# LED_Chaser.net
KiCad netlist of a schematic drawn in Altium Designer
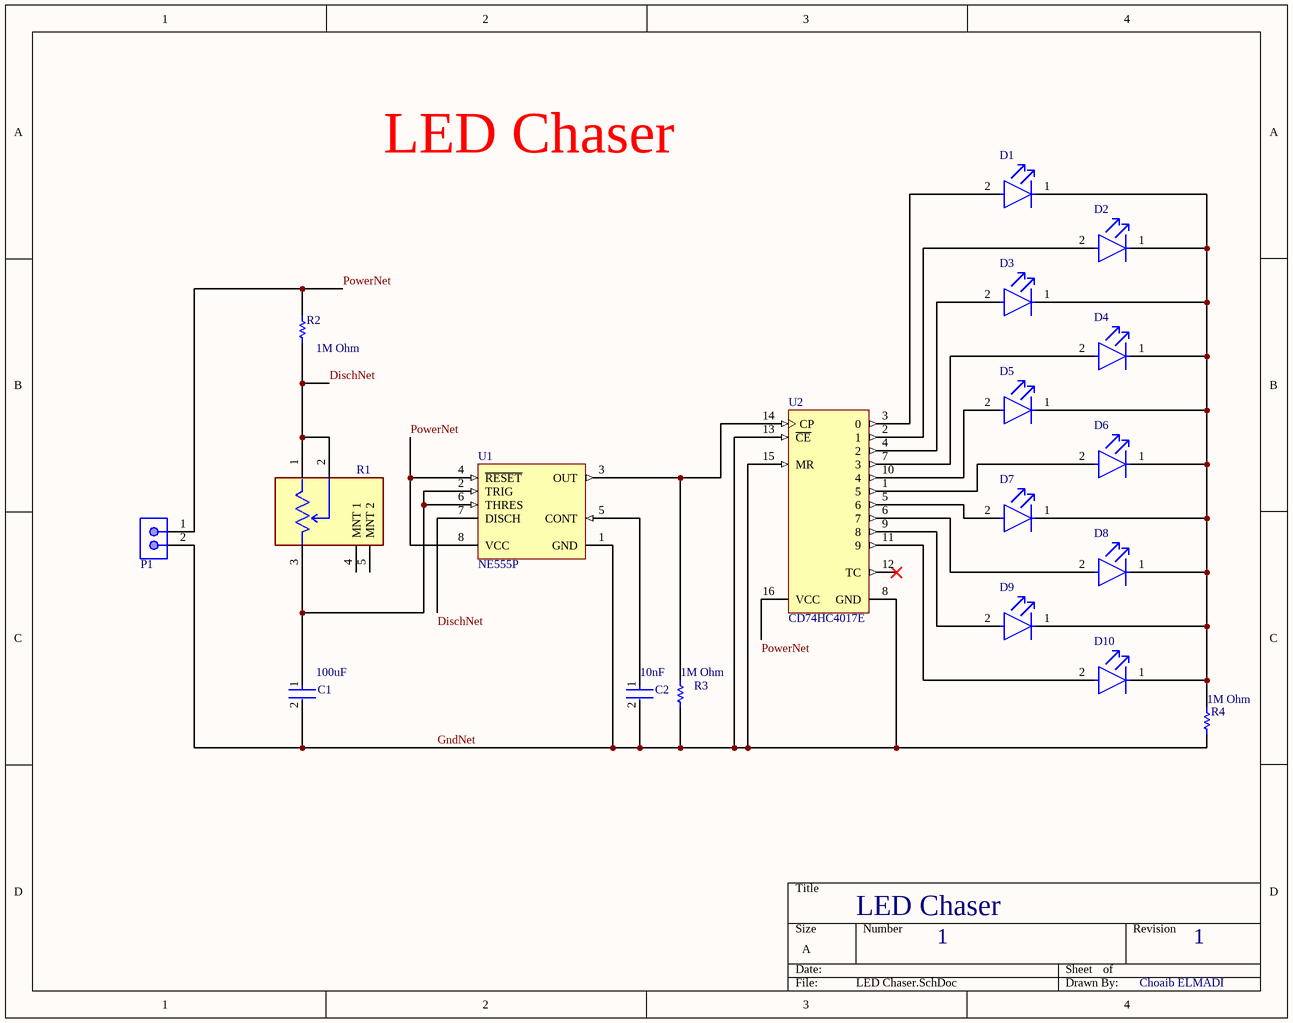
[diagram p0: LED Chaser.SchDoc]

(export (version "E")
  (design (tool "Eeschema 10.0.6"))
  (components
    (comp (ref "C1")
      (value "GRM32ER60J107ME20L")
      (footprint "FP-GRM32-0_3-MFG")
      (description "CAP CER 100UF 6.3V X5R 1210")
      (fields
        (field (name "OCTOPART") "https://octopart.com/grm32er60j107me20l-murata-197007")
        (field (name "3DS PART NUMBER") "220-00002")
        (field (name "CAPACITANCE") "100uF")
      )
      (libsource (lib "Altium Content Vault") (part "11868f565c42a9108669ba33697ecf6"))
    )
    (comp (ref "C2")
      (value "GRM32ER60J107ME20L")
      (footprint "FP-GRM32-0_3-MFG")
      (description "CAP CER 100UF 6.3V X5R 1210")
      (fields
        (field (name "OCTOPART") "https://octopart.com/grm32er60j107me20l-murata-197007")
        (field (name "3DS PART NUMBER") "220-00002")
        (field (name "CAPACITANCE") "10nF")
      )
      (libsource (lib "Altium Content Vault") (part "11868f565c42a9108669ba33697ecf6"))
    )
    (comp (ref "D1")
      (value "TLHR4400")
      (footprint "FP-6_544-5255_01-4-MFG")
      (description "TLHR4400 LED; Red; 3mcd; 3mmDia.; T-1; 30mA; 2V; 635nm; +/-30deg; GaAsP on GaP; 15V; 100mW")
      (libsource (lib "Altium Content Vault") (part "8706943c75ba83719d021d2fdc84c58"))
    )
    (comp (ref "D2")
      (value "TLHR4400")
      (footprint "FP-6_544-5255_01-4-MFG")
      (description "TLHR4400 LED; Red; 3mcd; 3mmDia.; T-1; 30mA; 2V; 635nm; +/-30deg; GaAsP on GaP; 15V; 100mW")
      (libsource (lib "Altium Content Vault") (part "8706943c75ba83719d021d2fdc84c58"))
    )
    (comp (ref "D3")
      (value "TLHR4400")
      (footprint "FP-6_544-5255_01-4-MFG")
      (description "TLHR4400 LED; Red; 3mcd; 3mmDia.; T-1; 30mA; 2V; 635nm; +/-30deg; GaAsP on GaP; 15V; 100mW")
      (libsource (lib "Altium Content Vault") (part "8706943c75ba83719d021d2fdc84c58"))
    )
    (comp (ref "D4")
      (value "TLHR4400")
      (footprint "FP-6_544-5255_01-4-MFG")
      (description "TLHR4400 LED; Red; 3mcd; 3mmDia.; T-1; 30mA; 2V; 635nm; +/-30deg; GaAsP on GaP; 15V; 100mW")
      (libsource (lib "Altium Content Vault") (part "8706943c75ba83719d021d2fdc84c58"))
    )
    (comp (ref "D5")
      (value "TLHR4400")
      (footprint "FP-6_544-5255_01-4-MFG")
      (description "TLHR4400 LED; Red; 3mcd; 3mmDia.; T-1; 30mA; 2V; 635nm; +/-30deg; GaAsP on GaP; 15V; 100mW")
      (libsource (lib "Altium Content Vault") (part "8706943c75ba83719d021d2fdc84c58"))
    )
    (comp (ref "D6")
      (value "TLHR4400")
      (footprint "FP-6_544-5255_01-4-MFG")
      (description "TLHR4400 LED; Red; 3mcd; 3mmDia.; T-1; 30mA; 2V; 635nm; +/-30deg; GaAsP on GaP; 15V; 100mW")
      (libsource (lib "Altium Content Vault") (part "8706943c75ba83719d021d2fdc84c58"))
    )
    (comp (ref "D7")
      (value "TLHR4400")
      (footprint "FP-6_544-5255_01-4-MFG")
      (description "TLHR4400 LED; Red; 3mcd; 3mmDia.; T-1; 30mA; 2V; 635nm; +/-30deg; GaAsP on GaP; 15V; 100mW")
      (libsource (lib "Altium Content Vault") (part "8706943c75ba83719d021d2fdc84c58"))
    )
    (comp (ref "D8")
      (value "TLHR4400")
      (footprint "FP-6_544-5255_01-4-MFG")
      (description "TLHR4400 LED; Red; 3mcd; 3mmDia.; T-1; 30mA; 2V; 635nm; +/-30deg; GaAsP on GaP; 15V; 100mW")
      (libsource (lib "Altium Content Vault") (part "8706943c75ba83719d021d2fdc84c58"))
    )
    (comp (ref "D9")
      (value "TLHR4400")
      (footprint "FP-6_544-5255_01-4-MFG")
      (description "TLHR4400 LED; Red; 3mcd; 3mmDia.; T-1; 30mA; 2V; 635nm; +/-30deg; GaAsP on GaP; 15V; 100mW")
      (libsource (lib "Altium Content Vault") (part "8706943c75ba83719d021d2fdc84c58"))
    )
    (comp (ref "D10")
      (value "TLHR4400")
      (footprint "FP-6_544-5255_01-4-MFG")
      (description "TLHR4400 LED; Red; 3mcd; 3mmDia.; T-1; 30mA; 2V; 635nm; +/-30deg; GaAsP on GaP; 15V; 100mW")
      (libsource (lib "Altium Content Vault") (part "8706943c75ba83719d021d2fdc84c58"))
    )
    (comp (ref "P1")
      (value "5-146280-2")
      (footprint "TECO-5-146280-2_V")
      (fields (field (name "MANUFACTURER") "TE Connectivity"))
      (libsource (lib "Altium Content Vault") (part "CN-1P-M-R2"))
    )
    (comp (ref "R1")
      (value "PTV09A-4225F-B103")
      (footprint "FP-PTV09A-4-MFG")
      (description "POT 10K OHM 1/20W CARBON LINEAR")
      (fields (field (name "TOLERANCE") "20%"))
      (libsource (lib "Altium Content Vault") (part "705d11b747745a787204d796a5f3d12"))
    )
    (comp (ref "R2")
      (value "MFR-25FBF52-1M")
      (footprint "RESA60-630X240")
      (description "Axial Resistor, 1 MOhm, +/- 1%, 250 mW, -55 to 155 degC, 2-Pin THD, RoHS, Bulk")
      (fields (field (name "RESISTANCE") "1M Ohm") (field (name "TOLERANCE") "1%"))
      (libsource (lib "Altium Content Vault") (part "RES-2"))
    )
    (comp (ref "R3")
      (value "MFR-25FBF52-1M")
      (footprint "RESA60-630X240")
      (description "Axial Resistor, 1 MOhm, +/- 1%, 250 mW, -55 to 155 degC, 2-Pin THD, RoHS, Bulk")
      (fields (field (name "RESISTANCE") "1M Ohm") (field (name "TOLERANCE") "1%"))
      (libsource (lib "Altium Content Vault") (part "RES-2"))
    )
    (comp (ref "R4")
      (value "MFR-25FBF52-1M")
      (footprint "RESA60-630X240")
      (description "Axial Resistor, 1 MOhm, +/- 1%, 250 mW, -55 to 155 degC, 2-Pin THD, RoHS, Bulk")
      (fields (field (name "RESISTANCE") "1M Ohm") (field (name "TOLERANCE") "1%"))
      (libsource (lib "Altium Content Vault") (part "RES-2"))
    )
    (comp (ref "U1")
      (value "NE555P")
      (footprint "P0008A")
      (description "Precision Timer, 4.5 to 16 V, 0 to 70 degC, 8-Pin DIP, Pb-Free, Tube")
      (fields (field (name "MANUFACTURER") "TexasInstruments"))
      (libsource (lib "Altium Content Vault") (part "TI-NE555-P8"))
    )
    (comp (ref "U2")
      (value "CD74HC4017E")
      (footprint "N0016A")
      (description "High Speed CMOS Logic Decade Counter/Divider with 10 Decoded Outputs, N0016A, TUBE")
      (fields
        (field (name "GENERIC PART NUMBER") "CD74HC4017")
        (field (name "MANUFACTURER") "Texas Instruments")
      )
      (libsource (lib "Altium Content Vault") (part "TI-CD74HC4017-16"))
    )
  )
  (nets
    (net (code "1") (name "/DischNet") (class "Default")
      (node (ref "R1") (pin "1") (pinfunction "1_1") (pintype "passive"))
      (node (ref "R1") (pin "2") (pinfunction "2_2") (pintype "passive"))
      (node (ref "R2") (pin "1") (pinfunction "1_1") (pintype "passive"))
      (node (ref "U1") (pin "7") (pinfunction "DISCH_7") (pintype "open_collector"))
    )
    (net (code "2") (name "/GndNet") (class "Default")
      (node (ref "C1") (pin "2") (pinfunction "2_2") (pintype "passive"))
      (node (ref "C2") (pin "2") (pinfunction "2_2") (pintype "passive"))
      (node (ref "P1") (pin "2") (pinfunction "2_2") (pintype "passive"))
      (node (ref "R3") (pin "1") (pinfunction "1_1") (pintype "passive"))
      (node (ref "R4") (pin "1") (pinfunction "1_1") (pintype "passive"))
      (node (ref "U1") (pin "1") (pinfunction "GND_1") (pintype "power_in"))
      (node (ref "U2") (pin "13") (pinfunction "~{CE}_13") (pintype "input"))
      (node (ref "U2") (pin "15") (pinfunction "MR_15") (pintype "input"))
      (node (ref "U2") (pin "8") (pinfunction "GND_8") (pintype "power_in"))
    )
    (net (code "3") (name "/PowerNet") (class "Default")
      (node (ref "P1") (pin "1") (pinfunction "1_1") (pintype "passive"))
      (node (ref "R2") (pin "2") (pinfunction "2_2") (pintype "passive"))
      (node (ref "U1") (pin "4") (pinfunction "~{RESET}_4") (pintype "input"))
      (node (ref "U1") (pin "8") (pinfunction "VCC_8") (pintype "power_in"))
      (node (ref "U2") (pin "16") (pinfunction "VCC_16") (pintype "power_in"))
    )
    (net (code "4") (name "Net-(D1-A)") (class "Default")
      (node (ref "D1") (pin "2") (pinfunction "A_2") (pintype "passive"))
      (node (ref "U2") (pin "3") (pinfunction "0_3") (pintype "output"))
    )
    (net (code "5") (name "Net-(D1-C)") (class "Default")
      (node (ref "D1") (pin "1") (pinfunction "C_1") (pintype "passive"))
      (node (ref "D10") (pin "1") (pinfunction "C_1") (pintype "passive"))
      (node (ref "D2") (pin "1") (pinfunction "C_1") (pintype "passive"))
      (node (ref "D3") (pin "1") (pinfunction "C_1") (pintype "passive"))
      (node (ref "D4") (pin "1") (pinfunction "C_1") (pintype "passive"))
      (node (ref "D5") (pin "1") (pinfunction "C_1") (pintype "passive"))
      (node (ref "D6") (pin "1") (pinfunction "C_1") (pintype "passive"))
      (node (ref "D7") (pin "1") (pinfunction "C_1") (pintype "passive"))
      (node (ref "D8") (pin "1") (pinfunction "C_1") (pintype "passive"))
      (node (ref "D9") (pin "1") (pinfunction "C_1") (pintype "passive"))
      (node (ref "R4") (pin "2") (pinfunction "2_2") (pintype "passive"))
    )
    (net (code "6") (name "Net-(D2-A)") (class "Default")
      (node (ref "D2") (pin "2") (pinfunction "A_2") (pintype "passive"))
      (node (ref "U2") (pin "2") (pinfunction "1_2") (pintype "output"))
    )
    (net (code "7") (name "Net-(D3-A)") (class "Default")
      (node (ref "D3") (pin "2") (pinfunction "A_2") (pintype "passive"))
      (node (ref "U2") (pin "4") (pinfunction "2_4") (pintype "output"))
    )
    (net (code "8") (name "Net-(D4-A)") (class "Default")
      (node (ref "D4") (pin "2") (pinfunction "A_2") (pintype "passive"))
      (node (ref "U2") (pin "7") (pinfunction "3_7") (pintype "output"))
    )
    (net (code "9") (name "Net-(D5-A)") (class "Default")
      (node (ref "D5") (pin "2") (pinfunction "A_2") (pintype "passive"))
      (node (ref "U2") (pin "10") (pinfunction "4_10") (pintype "output"))
    )
    (net (code "10") (name "Net-(D6-A)") (class "Default")
      (node (ref "D6") (pin "2") (pinfunction "A_2") (pintype "passive"))
      (node (ref "U2") (pin "1") (pinfunction "5_1") (pintype "output"))
    )
    (net (code "11") (name "Net-(D7-A)") (class "Default")
      (node (ref "D7") (pin "2") (pinfunction "A_2") (pintype "passive"))
      (node (ref "U2") (pin "5") (pinfunction "6_5") (pintype "output"))
    )
    (net (code "12") (name "Net-(D8-A)") (class "Default")
      (node (ref "D8") (pin "2") (pinfunction "A_2") (pintype "passive"))
      (node (ref "U2") (pin "6") (pinfunction "7_6") (pintype "output"))
    )
    (net (code "13") (name "Net-(D9-A)") (class "Default")
      (node (ref "D9") (pin "2") (pinfunction "A_2") (pintype "passive"))
      (node (ref "U2") (pin "9") (pinfunction "8_9") (pintype "output"))
    )
    (net (code "14") (name "Net-(D10-A)") (class "Default")
      (node (ref "D10") (pin "2") (pinfunction "A_2") (pintype "passive"))
      (node (ref "U2") (pin "11") (pinfunction "9_11") (pintype "output"))
    )
    (net (code "15") (name "Net-(U1-CONT)") (class "Default")
      (node (ref "C2") (pin "1") (pinfunction "1_1") (pintype "passive"))
      (node (ref "U1") (pin "5") (pinfunction "CONT_5") (pintype "input"))
    )
    (net (code "16") (name "Net-(U1-OUT)") (class "Default")
      (node (ref "R3") (pin "2") (pinfunction "2_2") (pintype "passive"))
      (node (ref "U1") (pin "3") (pinfunction "OUT_3") (pintype "output"))
      (node (ref "U2") (pin "14") (pinfunction "CP_14") (pintype "input"))
    )
    (net (code "17") (name "Net-(U1-THRES)") (class "Default")
      (node (ref "C1") (pin "1") (pinfunction "1_1") (pintype "passive"))
      (node (ref "R1") (pin "3") (pinfunction "3_3") (pintype "passive"))
      (node (ref "U1") (pin "2") (pinfunction "TRIG_2") (pintype "input"))
      (node (ref "U1") (pin "6") (pinfunction "THRES_6") (pintype "input"))
    )
    (net (code "18") (name "unconnected-(R1-MNT_1-Pad4)") (class "Default")
      (node (ref "R1") (pin "4") (pinfunction "MNT_1_4") (pintype "passive"))
    )
    (net (code "19") (name "unconnected-(R1-MNT_2-Pad5)") (class "Default")
      (node (ref "R1") (pin "5") (pinfunction "MNT_2_5") (pintype "passive"))
    )
    (net (code "20") (name "unconnected-(U2-TC-Pad12)") (class "Default")
      (node (ref "U2") (pin "12") (pinfunction "TC_12") (pintype "output+no_connect"))
    )
  )
)
